# Logic.net
KiCad netlist of a schematic drawn in Altium Designer
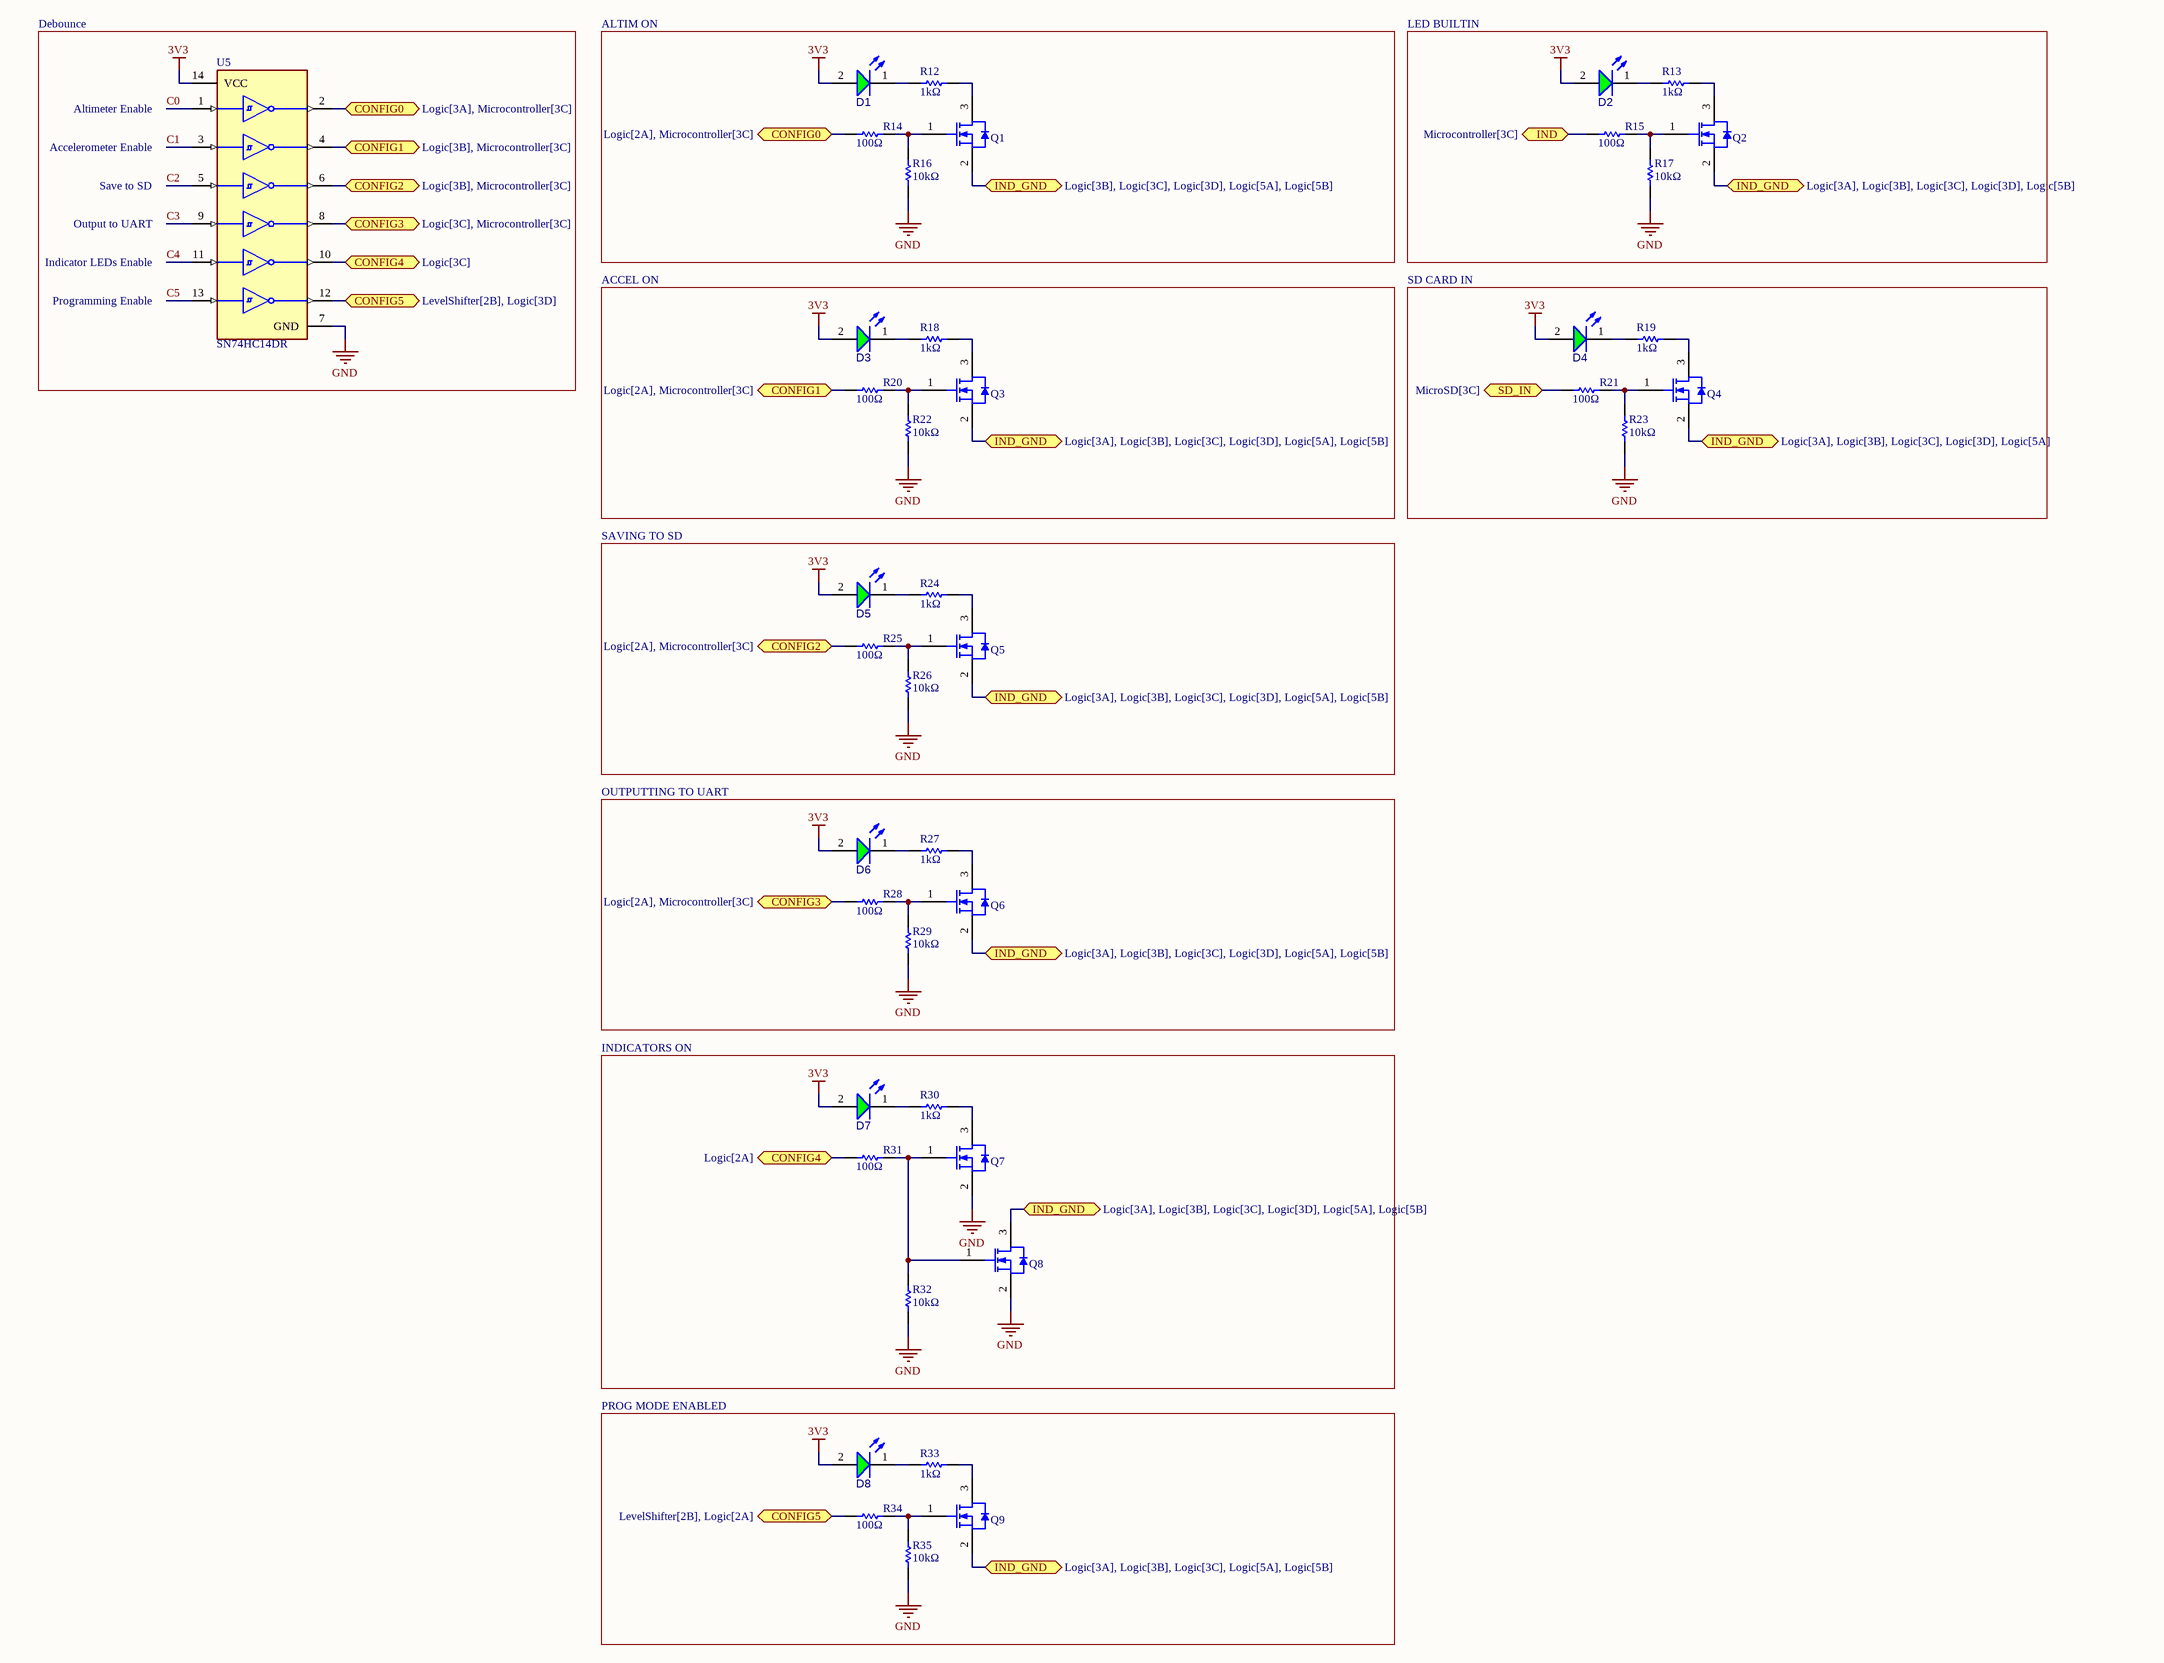
[diagram p0: Logic.SchDoc]

(export (version "E")
  (design (tool "Eeschema 10.0.6"))
  (components
    (comp (ref "D1")
      (value "150120GS75000")
      (footprint "WL-SMCW_1206_150120xx75000")
      (description "WL-SMCW SMT Mono-Color Chip LED Waterclear")
      (libsource (lib "Altium Content Vault") (part "LED_Green_2A-1K"))
    )
    (comp (ref "D2")
      (value "150120GS75000")
      (footprint "WL-SMCW_1206_150120xx75000")
      (description "WL-SMCW SMT Mono-Color Chip LED Waterclear")
      (libsource (lib "Altium Content Vault") (part "LED_Green_2A-1K"))
    )
    (comp (ref "D3")
      (value "150120GS75000")
      (footprint "WL-SMCW_1206_150120xx75000")
      (description "WL-SMCW SMT Mono-Color Chip LED Waterclear")
      (libsource (lib "Altium Content Vault") (part "LED_Green_2A-1K"))
    )
    (comp (ref "D4")
      (value "150120GS75000")
      (footprint "WL-SMCW_1206_150120xx75000")
      (description "WL-SMCW SMT Mono-Color Chip LED Waterclear")
      (libsource (lib "Altium Content Vault") (part "LED_Green_2A-1K"))
    )
    (comp (ref "D5")
      (value "150120GS75000")
      (footprint "WL-SMCW_1206_150120xx75000")
      (description "WL-SMCW SMT Mono-Color Chip LED Waterclear")
      (libsource (lib "Altium Content Vault") (part "LED_Green_2A-1K"))
    )
    (comp (ref "D6")
      (value "150120GS75000")
      (footprint "WL-SMCW_1206_150120xx75000")
      (description "WL-SMCW SMT Mono-Color Chip LED Waterclear")
      (libsource (lib "Altium Content Vault") (part "LED_Green_2A-1K"))
    )
    (comp (ref "D7")
      (value "150120GS75000")
      (footprint "WL-SMCW_1206_150120xx75000")
      (description "WL-SMCW SMT Mono-Color Chip LED Waterclear")
      (libsource (lib "Altium Content Vault") (part "LED_Green_2A-1K"))
    )
    (comp (ref "D8")
      (value "150120GS75000")
      (footprint "WL-SMCW_1206_150120xx75000")
      (description "WL-SMCW SMT Mono-Color Chip LED Waterclear")
      (libsource (lib "Altium Content Vault") (part "LED_Green_2A-1K"))
    )
    (comp (ref "Q1")
      (value "IRLML2502TRPBF")
      (footprint "INTR-SOT-23-3_V")
      (description "N-Channel HEXFET(R) Power MOSFET, 20 V VDS, +/- 12 V VGS, 4.2 A, 3-Pin SOT23, RoHS, Tape and Reel")
      (fields (field (name "MANUFACTURER") "International Rectifier"))
      (libsource (lib "Altium Content Vault") (part "NEMOS-GSD-3"))
    )
    (comp (ref "Q2")
      (value "IRLML2502TRPBF")
      (footprint "INTR-SOT-23-3_V")
      (description "N-Channel HEXFET(R) Power MOSFET, 20 V VDS, +/- 12 V VGS, 4.2 A, 3-Pin SOT23, RoHS, Tape and Reel")
      (fields (field (name "MANUFACTURER") "International Rectifier"))
      (libsource (lib "Altium Content Vault") (part "NEMOS-GSD-3"))
    )
    (comp (ref "Q3")
      (value "IRLML2502TRPBF")
      (footprint "INTR-SOT-23-3_V")
      (description "N-Channel HEXFET(R) Power MOSFET, 20 V VDS, +/- 12 V VGS, 4.2 A, 3-Pin SOT23, RoHS, Tape and Reel")
      (fields (field (name "MANUFACTURER") "International Rectifier"))
      (libsource (lib "Altium Content Vault") (part "NEMOS-GSD-3"))
    )
    (comp (ref "Q4")
      (value "IRLML2502TRPBF")
      (footprint "INTR-SOT-23-3_V")
      (description "N-Channel HEXFET(R) Power MOSFET, 20 V VDS, +/- 12 V VGS, 4.2 A, 3-Pin SOT23, RoHS, Tape and Reel")
      (fields (field (name "MANUFACTURER") "International Rectifier"))
      (libsource (lib "Altium Content Vault") (part "NEMOS-GSD-3"))
    )
    (comp (ref "Q5")
      (value "IRLML2502TRPBF")
      (footprint "INTR-SOT-23-3_V")
      (description "N-Channel HEXFET(R) Power MOSFET, 20 V VDS, +/- 12 V VGS, 4.2 A, 3-Pin SOT23, RoHS, Tape and Reel")
      (fields (field (name "MANUFACTURER") "International Rectifier"))
      (libsource (lib "Altium Content Vault") (part "NEMOS-GSD-3"))
    )
    (comp (ref "Q6")
      (value "IRLML2502TRPBF")
      (footprint "INTR-SOT-23-3_V")
      (description "N-Channel HEXFET(R) Power MOSFET, 20 V VDS, +/- 12 V VGS, 4.2 A, 3-Pin SOT23, RoHS, Tape and Reel")
      (fields (field (name "MANUFACTURER") "International Rectifier"))
      (libsource (lib "Altium Content Vault") (part "NEMOS-GSD-3"))
    )
    (comp (ref "Q7")
      (value "IRLML2502TRPBF")
      (footprint "INTR-SOT-23-3_V")
      (description "N-Channel HEXFET(R) Power MOSFET, 20 V VDS, +/- 12 V VGS, 4.2 A, 3-Pin SOT23, RoHS, Tape and Reel")
      (fields (field (name "MANUFACTURER") "International Rectifier"))
      (libsource (lib "Altium Content Vault") (part "NEMOS-GSD-3"))
    )
    (comp (ref "Q8")
      (value "IRLML2502TRPBF")
      (footprint "INTR-SOT-23-3_V")
      (description "N-Channel HEXFET(R) Power MOSFET, 20 V VDS, +/- 12 V VGS, 4.2 A, 3-Pin SOT23, RoHS, Tape and Reel")
      (fields (field (name "MANUFACTURER") "International Rectifier"))
      (libsource (lib "Altium Content Vault") (part "NEMOS-GSD-3"))
    )
    (comp (ref "Q9")
      (value "IRLML2502TRPBF")
      (footprint "INTR-SOT-23-3_V")
      (description "N-Channel HEXFET(R) Power MOSFET, 20 V VDS, +/- 12 V VGS, 4.2 A, 3-Pin SOT23, RoHS, Tape and Reel")
      (fields (field (name "MANUFACTURER") "International Rectifier"))
      (libsource (lib "Altium Content Vault") (part "NEMOS-GSD-3"))
    )
    (comp (ref "R12")
      (value "1kΩ")
      (footprint "RESC3116X65X40LL10T20")
      (description "Chip Resistor, 1 KOhm, +/- 1%, 0.25 W, -55 to 155 degC, 1206 (3216 Metric), RoHS, Tape and Reel")
      (fields (field (name "TOLERANCE") "1%") (field (name "MANUFACTURER") "Yageo"))
      (libsource (lib "Altium Content Vault") (part "RES-2"))
    )
    (comp (ref "R13")
      (value "1kΩ")
      (footprint "RESC3116X65X40LL10T20")
      (description "Chip Resistor, 1 KOhm, +/- 1%, 0.25 W, -55 to 155 degC, 1206 (3216 Metric), RoHS, Tape and Reel")
      (fields (field (name "TOLERANCE") "1%") (field (name "MANUFACTURER") "Yageo"))
      (libsource (lib "Altium Content Vault") (part "RES-2"))
    )
    (comp (ref "R14")
      (value "100Ω")
      (footprint "RESC3116X65X40LL10T20")
      (description "Chip Resistor, 100 Ohm, +/- 1%, 0.25 W, -55 to 155 degC, 1206 (3216 Metric), RoHS, Tape and Reel")
      (fields (field (name "MANUFACTURER") "Yageo") (field (name "TOLERANCE") "1%"))
      (libsource (lib "Altium Content Vault") (part "RES-2"))
    )
    (comp (ref "R15")
      (value "100Ω")
      (footprint "RESC3116X65X40LL10T20")
      (description "Chip Resistor, 100 Ohm, +/- 1%, 0.25 W, -55 to 155 degC, 1206 (3216 Metric), RoHS, Tape and Reel")
      (fields (field (name "MANUFACTURER") "Yageo") (field (name "TOLERANCE") "1%"))
      (libsource (lib "Altium Content Vault") (part "RES-2"))
    )
    (comp (ref "R16")
      (value "10kΩ")
      (footprint "RESC3116X65X40LL10T20")
      (description "Chip Resistor, 10 KOhm, +/- 1%, 0.25 W, -55 to 155 degC, 1206 (3216 Metric), RoHS, Tape and Reel")
      (fields (field (name "TOLERANCE") "1%") (field (name "MANUFACTURER") "Yageo"))
      (libsource (lib "Altium Content Vault") (part "RES-2"))
    )
    (comp (ref "R17")
      (value "10kΩ")
      (footprint "RESC3116X65X40LL10T20")
      (description "Chip Resistor, 10 KOhm, +/- 1%, 0.25 W, -55 to 155 degC, 1206 (3216 Metric), RoHS, Tape and Reel")
      (fields (field (name "TOLERANCE") "1%") (field (name "MANUFACTURER") "Yageo"))
      (libsource (lib "Altium Content Vault") (part "RES-2"))
    )
    (comp (ref "R18")
      (value "1kΩ")
      (footprint "RESC3116X65X40LL10T20")
      (description "Chip Resistor, 1 KOhm, +/- 1%, 0.25 W, -55 to 155 degC, 1206 (3216 Metric), RoHS, Tape and Reel")
      (fields (field (name "TOLERANCE") "1%") (field (name "MANUFACTURER") "Yageo"))
      (libsource (lib "Altium Content Vault") (part "RES-2"))
    )
    (comp (ref "R19")
      (value "1kΩ")
      (footprint "RESC3116X65X40LL10T20")
      (description "Chip Resistor, 1 KOhm, +/- 1%, 0.25 W, -55 to 155 degC, 1206 (3216 Metric), RoHS, Tape and Reel")
      (fields (field (name "TOLERANCE") "1%") (field (name "MANUFACTURER") "Yageo"))
      (libsource (lib "Altium Content Vault") (part "RES-2"))
    )
    (comp (ref "R20")
      (value "100Ω")
      (footprint "RESC3116X65X40LL10T20")
      (description "Chip Resistor, 100 Ohm, +/- 1%, 0.25 W, -55 to 155 degC, 1206 (3216 Metric), RoHS, Tape and Reel")
      (fields (field (name "MANUFACTURER") "Yageo") (field (name "TOLERANCE") "1%"))
      (libsource (lib "Altium Content Vault") (part "RES-2"))
    )
    (comp (ref "R21")
      (value "100Ω")
      (footprint "RESC3116X65X40LL10T20")
      (description "Chip Resistor, 100 Ohm, +/- 1%, 0.25 W, -55 to 155 degC, 1206 (3216 Metric), RoHS, Tape and Reel")
      (fields (field (name "MANUFACTURER") "Yageo") (field (name "TOLERANCE") "1%"))
      (libsource (lib "Altium Content Vault") (part "RES-2"))
    )
    (comp (ref "R22")
      (value "10kΩ")
      (footprint "RESC3116X65X40LL10T20")
      (description "Chip Resistor, 10 KOhm, +/- 1%, 0.25 W, -55 to 155 degC, 1206 (3216 Metric), RoHS, Tape and Reel")
      (fields (field (name "TOLERANCE") "1%") (field (name "MANUFACTURER") "Yageo"))
      (libsource (lib "Altium Content Vault") (part "RES-2"))
    )
    (comp (ref "R23")
      (value "10kΩ")
      (footprint "RESC3116X65X40LL10T20")
      (description "Chip Resistor, 10 KOhm, +/- 1%, 0.25 W, -55 to 155 degC, 1206 (3216 Metric), RoHS, Tape and Reel")
      (fields (field (name "TOLERANCE") "1%") (field (name "MANUFACTURER") "Yageo"))
      (libsource (lib "Altium Content Vault") (part "RES-2"))
    )
    (comp (ref "R24")
      (value "1kΩ")
      (footprint "RESC3116X65X40LL10T20")
      (description "Chip Resistor, 1 KOhm, +/- 1%, 0.25 W, -55 to 155 degC, 1206 (3216 Metric), RoHS, Tape and Reel")
      (fields (field (name "TOLERANCE") "1%") (field (name "MANUFACTURER") "Yageo"))
      (libsource (lib "Altium Content Vault") (part "RES-2"))
    )
    (comp (ref "R25")
      (value "100Ω")
      (footprint "RESC3116X65X40LL10T20")
      (description "Chip Resistor, 100 Ohm, +/- 1%, 0.25 W, -55 to 155 degC, 1206 (3216 Metric), RoHS, Tape and Reel")
      (fields (field (name "MANUFACTURER") "Yageo") (field (name "TOLERANCE") "1%"))
      (libsource (lib "Altium Content Vault") (part "RES-2"))
    )
    (comp (ref "R26")
      (value "10kΩ")
      (footprint "RESC3116X65X40LL10T20")
      (description "Chip Resistor, 10 KOhm, +/- 1%, 0.25 W, -55 to 155 degC, 1206 (3216 Metric), RoHS, Tape and Reel")
      (fields (field (name "TOLERANCE") "1%") (field (name "MANUFACTURER") "Yageo"))
      (libsource (lib "Altium Content Vault") (part "RES-2"))
    )
    (comp (ref "R27")
      (value "1kΩ")
      (footprint "RESC3116X65X40LL10T20")
      (description "Chip Resistor, 1 KOhm, +/- 1%, 0.25 W, -55 to 155 degC, 1206 (3216 Metric), RoHS, Tape and Reel")
      (fields (field (name "TOLERANCE") "1%") (field (name "MANUFACTURER") "Yageo"))
      (libsource (lib "Altium Content Vault") (part "RES-2"))
    )
    (comp (ref "R28")
      (value "100Ω")
      (footprint "RESC3116X65X40LL10T20")
      (description "Chip Resistor, 100 Ohm, +/- 1%, 0.25 W, -55 to 155 degC, 1206 (3216 Metric), RoHS, Tape and Reel")
      (fields (field (name "MANUFACTURER") "Yageo") (field (name "TOLERANCE") "1%"))
      (libsource (lib "Altium Content Vault") (part "RES-2"))
    )
    (comp (ref "R29")
      (value "10kΩ")
      (footprint "RESC3116X65X40LL10T20")
      (description "Chip Resistor, 10 KOhm, +/- 1%, 0.25 W, -55 to 155 degC, 1206 (3216 Metric), RoHS, Tape and Reel")
      (fields (field (name "TOLERANCE") "1%") (field (name "MANUFACTURER") "Yageo"))
      (libsource (lib "Altium Content Vault") (part "RES-2"))
    )
    (comp (ref "R30")
      (value "1kΩ")
      (footprint "RESC3116X65X40LL10T20")
      (description "Chip Resistor, 1 KOhm, +/- 1%, 0.25 W, -55 to 155 degC, 1206 (3216 Metric), RoHS, Tape and Reel")
      (fields (field (name "TOLERANCE") "1%") (field (name "MANUFACTURER") "Yageo"))
      (libsource (lib "Altium Content Vault") (part "RES-2"))
    )
    (comp (ref "R31")
      (value "100Ω")
      (footprint "RESC3116X65X40LL10T20")
      (description "Chip Resistor, 100 Ohm, +/- 1%, 0.25 W, -55 to 155 degC, 1206 (3216 Metric), RoHS, Tape and Reel")
      (fields (field (name "MANUFACTURER") "Yageo") (field (name "TOLERANCE") "1%"))
      (libsource (lib "Altium Content Vault") (part "RES-2"))
    )
    (comp (ref "R32")
      (value "10kΩ")
      (footprint "RESC3116X65X40LL10T20")
      (description "Chip Resistor, 10 KOhm, +/- 1%, 0.25 W, -55 to 155 degC, 1206 (3216 Metric), RoHS, Tape and Reel")
      (fields (field (name "TOLERANCE") "1%") (field (name "MANUFACTURER") "Yageo"))
      (libsource (lib "Altium Content Vault") (part "RES-2"))
    )
    (comp (ref "R33")
      (value "1kΩ")
      (footprint "RESC3116X65X40LL10T20")
      (description "Chip Resistor, 1 KOhm, +/- 1%, 0.25 W, -55 to 155 degC, 1206 (3216 Metric), RoHS, Tape and Reel")
      (fields (field (name "TOLERANCE") "1%") (field (name "MANUFACTURER") "Yageo"))
      (libsource (lib "Altium Content Vault") (part "RES-2"))
    )
    (comp (ref "R34")
      (value "100Ω")
      (footprint "RESC3116X65X40LL10T20")
      (description "Chip Resistor, 100 Ohm, +/- 1%, 0.25 W, -55 to 155 degC, 1206 (3216 Metric), RoHS, Tape and Reel")
      (fields (field (name "MANUFACTURER") "Yageo") (field (name "TOLERANCE") "1%"))
      (libsource (lib "Altium Content Vault") (part "RES-2"))
    )
    (comp (ref "R35")
      (value "10kΩ")
      (footprint "RESC3116X65X40LL10T20")
      (description "Chip Resistor, 10 KOhm, +/- 1%, 0.25 W, -55 to 155 degC, 1206 (3216 Metric), RoHS, Tape and Reel")
      (fields (field (name "TOLERANCE") "1%") (field (name "MANUFACTURER") "Yageo"))
      (libsource (lib "Altium Content Vault") (part "RES-2"))
    )
    (comp (ref "U5")
      (value "SN74HC14DR")
      (footprint "FP-D0014A-IPC_C")
      (description "IC INVERTER SCHMITT 6CH 14SOIC")
      (libsource (lib "Altium Content Vault") (part "f055c5830596d9dd18238fccf55026f"))
    )
  )
  (nets
    (net (code "1") (name "/C0") (class "Default")
      (node (ref "U5") (pin "1") (pinfunction "1A_1") (pintype "input"))
    )
    (net (code "2") (name "/C1") (class "Default")
      (node (ref "U5") (pin "3") (pinfunction "2A_3") (pintype "input"))
    )
    (net (code "3") (name "/C2") (class "Default")
      (node (ref "U5") (pin "5") (pinfunction "3A_5") (pintype "input"))
    )
    (net (code "4") (name "/C3") (class "Default")
      (node (ref "U5") (pin "9") (pinfunction "4A_9") (pintype "input"))
    )
    (net (code "5") (name "/C4") (class "Default")
      (node (ref "U5") (pin "11") (pinfunction "5A_11") (pintype "input"))
    )
    (net (code "6") (name "/C5") (class "Default")
      (node (ref "U5") (pin "13") (pinfunction "6A_13") (pintype "input"))
    )
    (net (code "7") (name "/CONFIG0") (class "Default")
      (node (ref "R14") (pin "1") (pinfunction "1_1") (pintype "passive"))
      (node (ref "U5") (pin "2") (pinfunction "1Y_2") (pintype "output"))
    )
    (net (code "8") (name "/CONFIG1") (class "Default")
      (node (ref "R20") (pin "1") (pinfunction "1_1") (pintype "passive"))
      (node (ref "U5") (pin "4") (pinfunction "2Y_4") (pintype "output"))
    )
    (net (code "9") (name "/CONFIG2") (class "Default")
      (node (ref "R25") (pin "1") (pinfunction "1_1") (pintype "passive"))
      (node (ref "U5") (pin "6") (pinfunction "3Y_6") (pintype "output"))
    )
    (net (code "10") (name "/CONFIG3") (class "Default")
      (node (ref "R28") (pin "1") (pinfunction "1_1") (pintype "passive"))
      (node (ref "U5") (pin "8") (pinfunction "4Y_8") (pintype "output"))
    )
    (net (code "11") (name "/CONFIG4") (class "Default")
      (node (ref "R31") (pin "1") (pinfunction "1_1") (pintype "passive"))
      (node (ref "U5") (pin "10") (pinfunction "5Y_10") (pintype "output"))
    )
    (net (code "12") (name "/CONFIG5") (class "Default")
      (node (ref "R34") (pin "1") (pinfunction "1_1") (pintype "passive"))
      (node (ref "U5") (pin "12") (pinfunction "6Y_12") (pintype "output"))
    )
    (net (code "13") (name "/IND") (class "Default")
      (node (ref "R15") (pin "1") (pinfunction "1_1") (pintype "passive"))
    )
    (net (code "14") (name "/IND_GND") (class "Default")
      (node (ref "Q1") (pin "2") (pinfunction "S_2") (pintype "passive"))
      (node (ref "Q2") (pin "2") (pinfunction "S_2") (pintype "passive"))
      (node (ref "Q3") (pin "2") (pinfunction "S_2") (pintype "passive"))
      (node (ref "Q4") (pin "2") (pinfunction "S_2") (pintype "passive"))
      (node (ref "Q5") (pin "2") (pinfunction "S_2") (pintype "passive"))
      (node (ref "Q6") (pin "2") (pinfunction "S_2") (pintype "passive"))
      (node (ref "Q8") (pin "3") (pinfunction "D_3") (pintype "passive"))
      (node (ref "Q9") (pin "2") (pinfunction "S_2") (pintype "passive"))
    )
    (net (code "15") (name "/SD_IN") (class "Default")
      (node (ref "R21") (pin "1") (pinfunction "1_1") (pintype "passive"))
    )
    (net (code "16") (name "3V3") (class "Default")
      (node (ref "D1") (pin "2") (pinfunction "A_2") (pintype "passive"))
      (node (ref "D2") (pin "2") (pinfunction "A_2") (pintype "passive"))
      (node (ref "D3") (pin "2") (pinfunction "A_2") (pintype "passive"))
      (node (ref "D4") (pin "2") (pinfunction "A_2") (pintype "passive"))
      (node (ref "D5") (pin "2") (pinfunction "A_2") (pintype "passive"))
      (node (ref "D6") (pin "2") (pinfunction "A_2") (pintype "passive"))
      (node (ref "D7") (pin "2") (pinfunction "A_2") (pintype "passive"))
      (node (ref "D8") (pin "2") (pinfunction "A_2") (pintype "passive"))
      (node (ref "U5") (pin "14") (pinfunction "VCC_14") (pintype "power_in"))
    )
    (net (code "17") (name "GND") (class "Default")
      (node (ref "Q7") (pin "2") (pinfunction "S_2") (pintype "passive"))
      (node (ref "Q8") (pin "2") (pinfunction "S_2") (pintype "passive"))
      (node (ref "R16") (pin "1") (pinfunction "1_1") (pintype "passive"))
      (node (ref "R17") (pin "1") (pinfunction "1_1") (pintype "passive"))
      (node (ref "R22") (pin "1") (pinfunction "1_1") (pintype "passive"))
      (node (ref "R23") (pin "1") (pinfunction "1_1") (pintype "passive"))
      (node (ref "R26") (pin "1") (pinfunction "1_1") (pintype "passive"))
      (node (ref "R29") (pin "1") (pinfunction "1_1") (pintype "passive"))
      (node (ref "R32") (pin "1") (pinfunction "1_1") (pintype "passive"))
      (node (ref "R35") (pin "1") (pinfunction "1_1") (pintype "passive"))
      (node (ref "U5") (pin "7") (pinfunction "GND_7") (pintype "power_in"))
    )
    (net (code "18") (name "Net-(D1-K)") (class "Default")
      (node (ref "D1") (pin "1") (pinfunction "K_1") (pintype "passive"))
      (node (ref "R12") (pin "2") (pinfunction "2_2") (pintype "passive"))
    )
    (net (code "19") (name "Net-(D2-K)") (class "Default")
      (node (ref "D2") (pin "1") (pinfunction "K_1") (pintype "passive"))
      (node (ref "R13") (pin "2") (pinfunction "2_2") (pintype "passive"))
    )
    (net (code "20") (name "Net-(D3-K)") (class "Default")
      (node (ref "D3") (pin "1") (pinfunction "K_1") (pintype "passive"))
      (node (ref "R18") (pin "2") (pinfunction "2_2") (pintype "passive"))
    )
    (net (code "21") (name "Net-(D4-K)") (class "Default")
      (node (ref "D4") (pin "1") (pinfunction "K_1") (pintype "passive"))
      (node (ref "R19") (pin "2") (pinfunction "2_2") (pintype "passive"))
    )
    (net (code "22") (name "Net-(D5-K)") (class "Default")
      (node (ref "D5") (pin "1") (pinfunction "K_1") (pintype "passive"))
      (node (ref "R24") (pin "2") (pinfunction "2_2") (pintype "passive"))
    )
    (net (code "23") (name "Net-(D6-K)") (class "Default")
      (node (ref "D6") (pin "1") (pinfunction "K_1") (pintype "passive"))
      (node (ref "R27") (pin "2") (pinfunction "2_2") (pintype "passive"))
    )
    (net (code "24") (name "Net-(D7-K)") (class "Default")
      (node (ref "D7") (pin "1") (pinfunction "K_1") (pintype "passive"))
      (node (ref "R30") (pin "2") (pinfunction "2_2") (pintype "passive"))
    )
    (net (code "25") (name "Net-(D8-K)") (class "Default")
      (node (ref "D8") (pin "1") (pinfunction "K_1") (pintype "passive"))
      (node (ref "R33") (pin "2") (pinfunction "2_2") (pintype "passive"))
    )
    (net (code "26") (name "Net-(Q1-D)") (class "Default")
      (node (ref "Q1") (pin "3") (pinfunction "D_3") (pintype "passive"))
      (node (ref "R12") (pin "1") (pinfunction "1_1") (pintype "passive"))
    )
    (net (code "27") (name "Net-(Q1-G)") (class "Default")
      (node (ref "Q1") (pin "1") (pinfunction "G_1") (pintype "passive"))
      (node (ref "R14") (pin "2") (pinfunction "2_2") (pintype "passive"))
      (node (ref "R16") (pin "2") (pinfunction "2_2") (pintype "passive"))
    )
    (net (code "28") (name "Net-(Q2-D)") (class "Default")
      (node (ref "Q2") (pin "3") (pinfunction "D_3") (pintype "passive"))
      (node (ref "R13") (pin "1") (pinfunction "1_1") (pintype "passive"))
    )
    (net (code "29") (name "Net-(Q2-G)") (class "Default")
      (node (ref "Q2") (pin "1") (pinfunction "G_1") (pintype "passive"))
      (node (ref "R15") (pin "2") (pinfunction "2_2") (pintype "passive"))
      (node (ref "R17") (pin "2") (pinfunction "2_2") (pintype "passive"))
    )
    (net (code "30") (name "Net-(Q3-D)") (class "Default")
      (node (ref "Q3") (pin "3") (pinfunction "D_3") (pintype "passive"))
      (node (ref "R18") (pin "1") (pinfunction "1_1") (pintype "passive"))
    )
    (net (code "31") (name "Net-(Q3-G)") (class "Default")
      (node (ref "Q3") (pin "1") (pinfunction "G_1") (pintype "passive"))
      (node (ref "R20") (pin "2") (pinfunction "2_2") (pintype "passive"))
      (node (ref "R22") (pin "2") (pinfunction "2_2") (pintype "passive"))
    )
    (net (code "32") (name "Net-(Q4-D)") (class "Default")
      (node (ref "Q4") (pin "3") (pinfunction "D_3") (pintype "passive"))
      (node (ref "R19") (pin "1") (pinfunction "1_1") (pintype "passive"))
    )
    (net (code "33") (name "Net-(Q4-G)") (class "Default")
      (node (ref "Q4") (pin "1") (pinfunction "G_1") (pintype "passive"))
      (node (ref "R21") (pin "2") (pinfunction "2_2") (pintype "passive"))
      (node (ref "R23") (pin "2") (pinfunction "2_2") (pintype "passive"))
    )
    (net (code "34") (name "Net-(Q5-D)") (class "Default")
      (node (ref "Q5") (pin "3") (pinfunction "D_3") (pintype "passive"))
      (node (ref "R24") (pin "1") (pinfunction "1_1") (pintype "passive"))
    )
    (net (code "35") (name "Net-(Q5-G)") (class "Default")
      (node (ref "Q5") (pin "1") (pinfunction "G_1") (pintype "passive"))
      (node (ref "R25") (pin "2") (pinfunction "2_2") (pintype "passive"))
      (node (ref "R26") (pin "2") (pinfunction "2_2") (pintype "passive"))
    )
    (net (code "36") (name "Net-(Q6-D)") (class "Default")
      (node (ref "Q6") (pin "3") (pinfunction "D_3") (pintype "passive"))
      (node (ref "R27") (pin "1") (pinfunction "1_1") (pintype "passive"))
    )
    (net (code "37") (name "Net-(Q6-G)") (class "Default")
      (node (ref "Q6") (pin "1") (pinfunction "G_1") (pintype "passive"))
      (node (ref "R28") (pin "2") (pinfunction "2_2") (pintype "passive"))
      (node (ref "R29") (pin "2") (pinfunction "2_2") (pintype "passive"))
    )
    (net (code "38") (name "Net-(Q7-D)") (class "Default")
      (node (ref "Q7") (pin "3") (pinfunction "D_3") (pintype "passive"))
      (node (ref "R30") (pin "1") (pinfunction "1_1") (pintype "passive"))
    )
    (net (code "39") (name "Net-(Q7-G)") (class "Default")
      (node (ref "Q7") (pin "1") (pinfunction "G_1") (pintype "passive"))
      (node (ref "Q8") (pin "1") (pinfunction "G_1") (pintype "passive"))
      (node (ref "R31") (pin "2") (pinfunction "2_2") (pintype "passive"))
      (node (ref "R32") (pin "2") (pinfunction "2_2") (pintype "passive"))
    )
    (net (code "40") (name "Net-(Q9-D)") (class "Default")
      (node (ref "Q9") (pin "3") (pinfunction "D_3") (pintype "passive"))
      (node (ref "R33") (pin "1") (pinfunction "1_1") (pintype "passive"))
    )
    (net (code "41") (name "Net-(Q9-G)") (class "Default")
      (node (ref "Q9") (pin "1") (pinfunction "G_1") (pintype "passive"))
      (node (ref "R34") (pin "2") (pinfunction "2_2") (pintype "passive"))
      (node (ref "R35") (pin "2") (pinfunction "2_2") (pintype "passive"))
    )
  )
)
